# adc-ic.net
KiCad netlist of a schematic drawn in Altium Designer
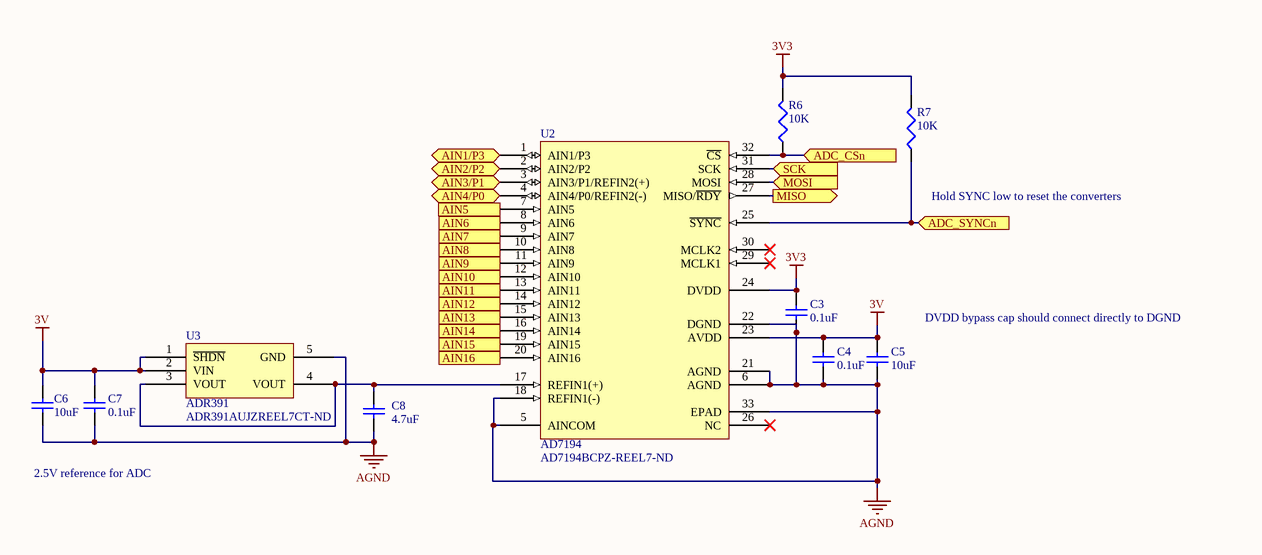
[diagram p0: adc-ic.SchDoc]

(export (version "E")
  (design (tool "Eeschema 10.0.6"))
  (components
    (comp (ref "C3")
      (value "0.1uF")
      (footprint "0402")
      (description "Capacitor (Semiconductor SIM Model)")
      (fields (field (name "PUBLISHER") "Altium Limited"))
      (libsource (lib "Miscellaneous Devices") (part "Cap Semi"))
    )
    (comp (ref "C4")
      (value "0.1uF")
      (footprint "0402")
      (description "Capacitor (Semiconductor SIM Model)")
      (fields (field (name "PUBLISHER") "Altium Limited"))
      (libsource (lib "Miscellaneous Devices") (part "Cap Semi"))
    )
    (comp (ref "C5")
      (value "10uF")
      (footprint "1608[0603]")
      (description "Capacitor (Semiconductor SIM Model)")
      (fields (field (name "PUBLISHER") "Altium Limited"))
      (libsource (lib "Miscellaneous Devices") (part "Cap Semi"))
    )
    (comp (ref "C6")
      (value "10uF")
      (footprint "1608[0603]")
      (description "Capacitor (Semiconductor SIM Model)")
      (fields (field (name "PUBLISHER") "Altium Limited"))
      (libsource (lib "Miscellaneous Devices") (part "Cap Semi"))
    )
    (comp (ref "C7")
      (value "0.1uF")
      (footprint "0402")
      (description "Capacitor (Semiconductor SIM Model)")
      (fields (field (name "PUBLISHER") "Altium Limited"))
      (libsource (lib "Miscellaneous Devices") (part "Cap Semi"))
    )
    (comp (ref "C8")
      (value "4.7uF")
      (footprint "1608[0603]")
      (description "Capacitor (Semiconductor SIM Model)")
      (fields (field (name "PUBLISHER") "Altium Limited"))
      (libsource (lib "Miscellaneous Devices") (part "Cap Semi"))
    )
    (comp (ref "R6")
      (value "10K")
      (footprint "0402")
      (description "Resistor")
      (fields (field (name "PUBLISHER") "Altium Limited"))
      (libsource (lib "Miscellaneous Devices") (part "Res3"))
    )
    (comp (ref "R7")
      (value "10K")
      (footprint "0402")
      (description "Resistor")
      (fields (field (name "PUBLISHER") "Altium Limited"))
      (libsource (lib "Miscellaneous Devices") (part "Res3"))
    )
    (comp (ref "U2")
      (value "AD7194")
      (description "24-bit sigma-delta ADC")
      (fields (field (name "SUPPLIER PART NUMBER 1") "AD7194BCPZ-REEL7-ND"))
      (libsource (lib "PAY") (part "AD7194"))
    )
    (comp (ref "U3")
      (value "ADR391")
      (footprint "SOT-23-5_95P290X160-5N")
      (description "2.5V reference voltage.")
      (fields (field (name "SUPPLIER PART NUMBER 1") "ADR391AUJZREEL7CT-ND"))
      (libsource (lib "PAY") (part "ADR391"))
    )
  )
  (nets
    (net (code "1") (name "/ADC_CSn") (class "Default")
      (node (ref "R6") (pin "1") (pinfunction "1_1") (pintype "passive"))
      (node (ref "U2") (pin "32") (pinfunction "~{CS}_32") (pintype "input"))
    )
    (net (code "2") (name "/ADC_SYNCn") (class "Default")
      (node (ref "R7") (pin "1") (pinfunction "1_1") (pintype "passive"))
      (node (ref "U2") (pin "25") (pinfunction "~{SYNC}_25") (pintype "input"))
    )
    (net (code "3") (name "/AIN1{slash}P3") (class "Default")
      (node (ref "U2") (pin "1") (pinfunction "AIN1/P3_1") (pintype "bidirectional"))
    )
    (net (code "4") (name "/AIN2{slash}P2") (class "Default")
      (node (ref "U2") (pin "2") (pinfunction "AIN2/P2_2") (pintype "bidirectional"))
    )
    (net (code "5") (name "/AIN3{slash}P1") (class "Default")
      (node (ref "U2") (pin "3") (pinfunction "AIN3/P1/REFIN2(+)_3") (pintype "bidirectional"))
    )
    (net (code "6") (name "/AIN4{slash}P0") (class "Default")
      (node (ref "U2") (pin "4") (pinfunction "AIN4/P0/REFIN2(-)_4") (pintype "bidirectional"))
    )
    (net (code "7") (name "/AIN5") (class "Default")
      (node (ref "U2") (pin "7") (pinfunction "AIN5_7") (pintype "input"))
    )
    (net (code "8") (name "/AIN6") (class "Default")
      (node (ref "U2") (pin "8") (pinfunction "AIN6_8") (pintype "input"))
    )
    (net (code "9") (name "/AIN7") (class "Default")
      (node (ref "U2") (pin "9") (pinfunction "AIN7_9") (pintype "input"))
    )
    (net (code "10") (name "/AIN8") (class "Default")
      (node (ref "U2") (pin "10") (pinfunction "AIN8_10") (pintype "input"))
    )
    (net (code "11") (name "/AIN9") (class "Default")
      (node (ref "U2") (pin "11") (pinfunction "AIN9_11") (pintype "input"))
    )
    (net (code "12") (name "/AIN10") (class "Default")
      (node (ref "U2") (pin "12") (pinfunction "AIN10_12") (pintype "input"))
    )
    (net (code "13") (name "/AIN11") (class "Default")
      (node (ref "U2") (pin "13") (pinfunction "AIN11_13") (pintype "input"))
    )
    (net (code "14") (name "/AIN12") (class "Default")
      (node (ref "U2") (pin "14") (pinfunction "AIN12_14") (pintype "input"))
    )
    (net (code "15") (name "/AIN13") (class "Default")
      (node (ref "U2") (pin "15") (pinfunction "AIN13_15") (pintype "input"))
    )
    (net (code "16") (name "/AIN14") (class "Default")
      (node (ref "U2") (pin "16") (pinfunction "AIN14_16") (pintype "input"))
    )
    (net (code "17") (name "/AIN15") (class "Default")
      (node (ref "U2") (pin "19") (pinfunction "AIN15_19") (pintype "input"))
    )
    (net (code "18") (name "/AIN16") (class "Default")
      (node (ref "U2") (pin "20") (pinfunction "AIN16_20") (pintype "input"))
    )
    (net (code "19") (name "/MISO") (class "Default")
      (node (ref "U2") (pin "27") (pinfunction "MISO/~{RDY}_27") (pintype "output"))
    )
    (net (code "20") (name "/MOSI") (class "Default")
      (node (ref "U2") (pin "28") (pinfunction "MOSI_28") (pintype "input"))
    )
    (net (code "21") (name "/SCK") (class "Default")
      (node (ref "U2") (pin "31") (pinfunction "SCK_31") (pintype "input"))
    )
    (net (code "22") (name "3V") (class "Default")
      (node (ref "C4") (pin "2") (pinfunction "2_2") (pintype "passive"))
      (node (ref "C5") (pin "2") (pinfunction "2_2") (pintype "passive"))
      (node (ref "C6") (pin "2") (pinfunction "2_2") (pintype "passive"))
      (node (ref "C7") (pin "2") (pinfunction "2_2") (pintype "passive"))
      (node (ref "U2") (pin "23") (pinfunction "AVDD_23") (pintype "power_in"))
      (node (ref "U3") (pin "1") (pinfunction "~{SHDN}_1") (pintype "passive"))
      (node (ref "U3") (pin "2") (pinfunction "VIN_2") (pintype "passive"))
    )
    (net (code "23") (name "3V3") (class "Default")
      (node (ref "C3") (pin "2") (pinfunction "2_2") (pintype "passive"))
      (node (ref "R6") (pin "2") (pinfunction "2_2") (pintype "passive"))
      (node (ref "R7") (pin "2") (pinfunction "2_2") (pintype "passive"))
      (node (ref "U2") (pin "24") (pinfunction "DVDD_24") (pintype "power_in"))
    )
    (net (code "24") (name "AGND") (class "Default")
      (node (ref "C3") (pin "1") (pinfunction "1_1") (pintype "passive"))
      (node (ref "C4") (pin "1") (pinfunction "1_1") (pintype "passive"))
      (node (ref "C5") (pin "1") (pinfunction "1_1") (pintype "passive"))
      (node (ref "C6") (pin "1") (pinfunction "1_1") (pintype "passive"))
      (node (ref "C7") (pin "1") (pinfunction "1_1") (pintype "passive"))
      (node (ref "C8") (pin "1") (pinfunction "1_1") (pintype "passive"))
      (node (ref "U2") (pin "18") (pinfunction "REFIN1(-)_18") (pintype "input"))
      (node (ref "U2") (pin "21") (pinfunction "AGND_21") (pintype "power_in"))
      (node (ref "U2") (pin "22") (pinfunction "DGND_22") (pintype "power_in"))
      (node (ref "U2") (pin "33") (pinfunction "EPAD_33") (pintype "passive"))
      (node (ref "U2") (pin "5") (pinfunction "AINCOM_5") (pintype "power_in"))
      (node (ref "U2") (pin "6") (pinfunction "AGND_6") (pintype "power_in"))
      (node (ref "U3") (pin "5") (pinfunction "GND_5") (pintype "passive"))
    )
    (net (code "25") (name "Net-(U2-REFIN1(+))") (class "Default")
      (node (ref "C8") (pin "2") (pinfunction "2_2") (pintype "passive"))
      (node (ref "U2") (pin "17") (pinfunction "REFIN1(+)_17") (pintype "input"))
      (node (ref "U3") (pin "3") (pinfunction "VOUT_3") (pintype "passive"))
      (node (ref "U3") (pin "4") (pinfunction "VOUT_4") (pintype "passive"))
    )
    (net (code "26") (name "unconnected-(U2-MCLK1-Pad29)") (class "Default")
      (node (ref "U2") (pin "29") (pinfunction "MCLK1_29") (pintype "input+no_connect"))
    )
    (net (code "27") (name "unconnected-(U2-MCLK2-Pad30)") (class "Default")
      (node (ref "U2") (pin "30") (pinfunction "MCLK2_30") (pintype "input+no_connect"))
    )
    (net (code "28") (name "unconnected-(U2-NC-Pad26)") (class "Default")
      (node (ref "U2") (pin "26") (pinfunction "NC_26") (pintype "passive+no_connect"))
    )
  )
)
